# Slaves-Power-board.net
KiCad netlist of a schematic drawn in EAGLE
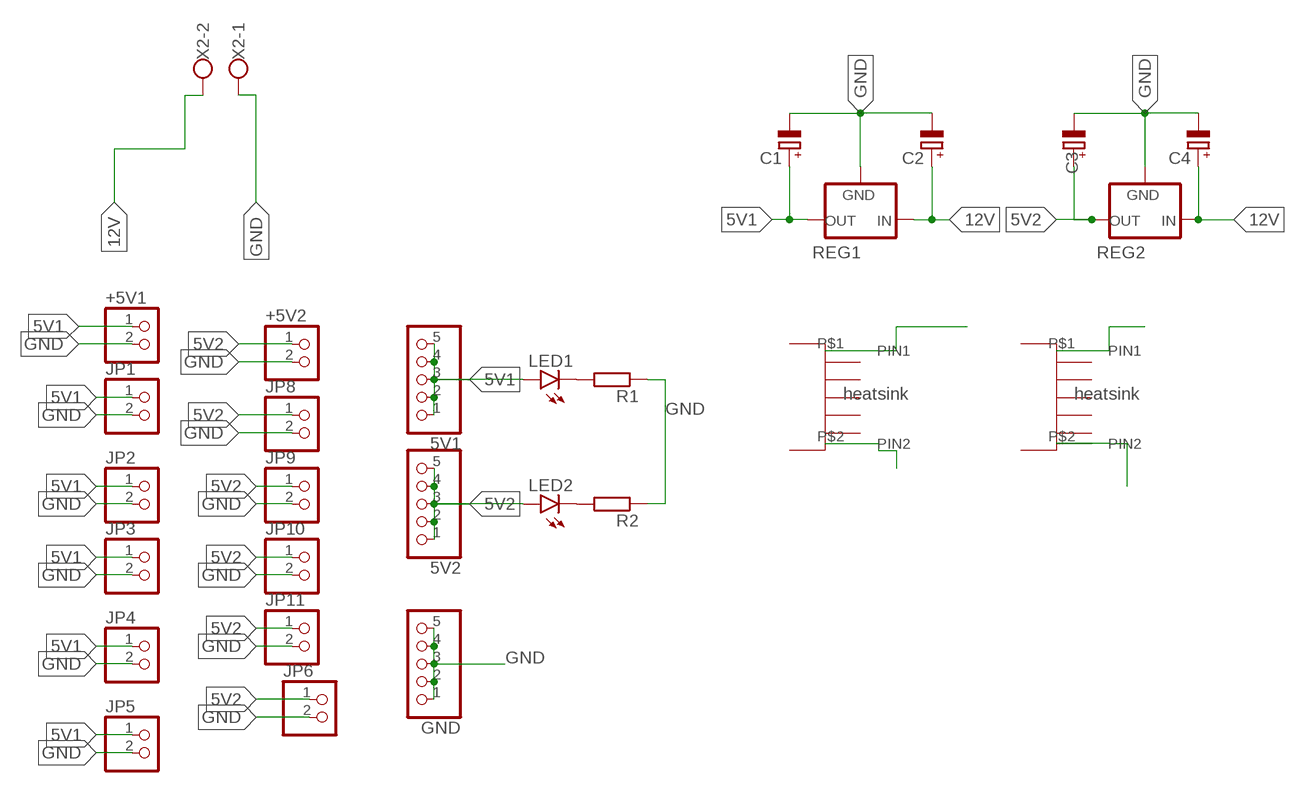
[diagram p0: schematic, sheet 1]

(export (version "E")
  (design (tool "Eeschema 10.0.6"))
  (components
    (comp (ref "+5V1")
      (value "PINHD-2_DATA")
      (footprint "eagle-import:1X02_DATA")
      (libsource (lib "eagle-import") (part "PINHD-2_DATA"))
    )
    (comp (ref "+5V2")
      (value "PINHD-2_DATA")
      (footprint "eagle-import:1X02_DATA")
      (libsource (lib "eagle-import") (part "PINHD-2_DATA"))
    )
    (comp (ref "5V1")
      (value "PINHD-1X5")
      (footprint "eagle-import:1X05")
      (libsource (lib "eagle-import") (part "PINHD-1X5"))
    )
    (comp (ref "5V2")
      (value "PINHD-1X5")
      (footprint "eagle-import:1X05")
      (libsource (lib "eagle-import") (part "PINHD-1X5"))
    )
    (comp (ref "C1")
      (value "CAP_POL")
      (footprint "eagle-import:E3,5-8")
      (libsource (lib "eagle-import") (part "CAP_POL"))
    )
    (comp (ref "C2")
      (value "CAP_POL")
      (footprint "eagle-import:E3,5-8")
      (libsource (lib "eagle-import") (part "CAP_POL"))
    )
    (comp (ref "C3")
      (value "CAP_POL")
      (footprint "eagle-import:E3,5-8")
      (libsource (lib "eagle-import") (part "CAP_POL"))
    )
    (comp (ref "C4")
      (value "CAP_POL")
      (footprint "eagle-import:E3,5-8")
      (libsource (lib "eagle-import") (part "CAP_POL"))
    )
    (comp (ref "GND")
      (value "PINHD-1X5")
      (footprint "eagle-import:1X05")
      (libsource (lib "eagle-import") (part "PINHD-1X5"))
    )
    (comp (ref "JP1")
      (value "PINHD-2_DATA")
      (footprint "eagle-import:1X02_DATA")
      (libsource (lib "eagle-import") (part "PINHD-2_DATA"))
    )
    (comp (ref "JP2")
      (value "PINHD-2_DATA")
      (footprint "eagle-import:1X02_DATA")
      (libsource (lib "eagle-import") (part "PINHD-2_DATA"))
    )
    (comp (ref "JP3")
      (value "PINHD-2_DATA")
      (footprint "eagle-import:1X02_DATA")
      (libsource (lib "eagle-import") (part "PINHD-2_DATA"))
    )
    (comp (ref "JP4")
      (value "PINHD-2_DATA")
      (footprint "eagle-import:1X02_DATA")
      (libsource (lib "eagle-import") (part "PINHD-2_DATA"))
    )
    (comp (ref "JP5")
      (value "PINHD-2_DATA")
      (footprint "eagle-import:1X02_DATA")
      (libsource (lib "eagle-import") (part "PINHD-2_DATA"))
    )
    (comp (ref "JP6")
      (value "PINHD-2_DATA")
      (footprint "eagle-import:1X02_DATA")
      (libsource (lib "eagle-import") (part "PINHD-2_DATA"))
    )
    (comp (ref "JP8")
      (value "PINHD-2_DATA")
      (footprint "eagle-import:1X02_DATA")
      (libsource (lib "eagle-import") (part "PINHD-2_DATA"))
    )
    (comp (ref "JP9")
      (value "PINHD-2_DATA")
      (footprint "eagle-import:1X02_DATA")
      (libsource (lib "eagle-import") (part "PINHD-2_DATA"))
    )
    (comp (ref "JP10")
      (value "PINHD-2_DATA")
      (footprint "eagle-import:1X02_DATA")
      (libsource (lib "eagle-import") (part "PINHD-2_DATA"))
    )
    (comp (ref "JP11")
      (value "PINHD-2_DATA")
      (footprint "eagle-import:1X02_DATA")
      (libsource (lib "eagle-import") (part "PINHD-2_DATA"))
    )
    (comp (ref "LED1")
      (value "LED5MM")
      (footprint "eagle-import:LED5MM")
      (libsource (lib "eagle-import") (part "LED5MM"))
    )
    (comp (ref "LED2")
      (value "LED5MM")
      (footprint "eagle-import:LED5MM")
      (libsource (lib "eagle-import") (part "LED5MM"))
    )
    (comp (ref "R1")
      (value "R-EU_0204/7")
      (footprint "eagle-import:0204_7")
      (libsource (lib "eagle-import") (part "R-EU_0204/7"))
    )
    (comp (ref "R2")
      (value "R-EU_0204/7")
      (footprint "eagle-import:0204_7")
      (libsource (lib "eagle-import") (part "R-EU_0204/7"))
    )
    (comp (ref "REG1")
      (value "78XXS")
      (footprint "eagle-import:78XXS")
      (libsource (lib "eagle-import") (part "78XXS"))
    )
    (comp (ref "REG2")
      (value "78XXS")
      (footprint "eagle-import:78XXS")
      (libsource (lib "eagle-import") (part "78XXS"))
    )
    (comp (ref "U$1")
      (value "HEAT-SINK")
      (footprint "eagle-import:HEAT_SINK")
      (libsource (lib "eagle-import") (part "HEAT-SINK"))
    )
    (comp (ref "U$2")
      (value "HEAT-SINK")
      (footprint "eagle-import:HEAT_SINK")
      (libsource (lib "eagle-import") (part "HEAT-SINK"))
    )
    (comp (ref "X2")
      (value "ROSTA.POWER")
      (footprint "eagle-import:W239-302")
      (libsource (lib "eagle-import") (part "ROSTA.POWER"))
    )
  )
  (nets
    (net (code "1") (name "5V1") (class "Default")
      (node (ref "+5V1") (pin "1") (pinfunction "1_1") (pintype "passive"))
      (node (ref "5V1") (pin "1") (pinfunction "1_1") (pintype "passive"))
      (node (ref "5V1") (pin "2") (pinfunction "2_2") (pintype "passive"))
      (node (ref "5V1") (pin "3") (pinfunction "3_3") (pintype "passive"))
      (node (ref "5V1") (pin "4") (pinfunction "4_4") (pintype "passive"))
      (node (ref "5V1") (pin "5") (pinfunction "5_5") (pintype "passive"))
      (node (ref "C1") (pin "+") (pinfunction "+_+") (pintype "passive"))
      (node (ref "JP1") (pin "1") (pinfunction "1_1") (pintype "passive"))
      (node (ref "JP2") (pin "1") (pinfunction "1_1") (pintype "passive"))
      (node (ref "JP3") (pin "1") (pinfunction "1_1") (pintype "passive"))
      (node (ref "JP4") (pin "1") (pinfunction "1_1") (pintype "passive"))
      (node (ref "JP5") (pin "1") (pinfunction "1_1") (pintype "passive"))
      (node (ref "LED1") (pin "A") (pinfunction "A_A") (pintype "passive"))
      (node (ref "REG1") (pin "OUT") (pinfunction "OUT_OUT") (pintype "passive"))
    )
    (net (code "2") (name "5V2") (class "Default")
      (node (ref "+5V2") (pin "1") (pinfunction "1_1") (pintype "passive"))
      (node (ref "5V2") (pin "1") (pinfunction "1_1") (pintype "passive"))
      (node (ref "5V2") (pin "2") (pinfunction "2_2") (pintype "passive"))
      (node (ref "5V2") (pin "3") (pinfunction "3_3") (pintype "passive"))
      (node (ref "5V2") (pin "4") (pinfunction "4_4") (pintype "passive"))
      (node (ref "5V2") (pin "5") (pinfunction "5_5") (pintype "passive"))
      (node (ref "C3") (pin "+") (pinfunction "+_+") (pintype "passive"))
      (node (ref "JP10") (pin "1") (pinfunction "1_1") (pintype "passive"))
      (node (ref "JP11") (pin "1") (pinfunction "1_1") (pintype "passive"))
      (node (ref "JP6") (pin "1") (pinfunction "1_1") (pintype "passive"))
      (node (ref "JP8") (pin "1") (pinfunction "1_1") (pintype "passive"))
      (node (ref "JP9") (pin "1") (pinfunction "1_1") (pintype "passive"))
      (node (ref "LED2") (pin "A") (pinfunction "A_A") (pintype "passive"))
      (node (ref "REG2") (pin "OUT") (pinfunction "OUT_OUT") (pintype "passive"))
    )
    (net (code "3") (name "12V") (class "Default")
      (node (ref "C2") (pin "+") (pinfunction "+_+") (pintype "passive"))
      (node (ref "C4") (pin "+") (pinfunction "+_+") (pintype "passive"))
      (node (ref "REG1") (pin "IN") (pinfunction "IN_IN") (pintype "input"))
      (node (ref "REG2") (pin "IN") (pinfunction "IN_IN") (pintype "input"))
      (node (ref "X2") (pin "2") (pinfunction "KL_2") (pintype "passive"))
    )
    (net (code "4") (name "GND") (class "Default")
      (node (ref "+5V1") (pin "2") (pinfunction "2_2") (pintype "passive"))
      (node (ref "+5V2") (pin "2") (pinfunction "2_2") (pintype "passive"))
      (node (ref "C1") (pin "-") (pinfunction "-_-") (pintype "passive"))
      (node (ref "C2") (pin "-") (pinfunction "-_-") (pintype "passive"))
      (node (ref "C3") (pin "-") (pinfunction "-_-") (pintype "passive"))
      (node (ref "C4") (pin "-") (pinfunction "-_-") (pintype "passive"))
      (node (ref "GND") (pin "1") (pinfunction "1_1") (pintype "passive"))
      (node (ref "GND") (pin "2") (pinfunction "2_2") (pintype "passive"))
      (node (ref "GND") (pin "3") (pinfunction "3_3") (pintype "passive"))
      (node (ref "GND") (pin "4") (pinfunction "4_4") (pintype "passive"))
      (node (ref "GND") (pin "5") (pinfunction "5_5") (pintype "passive"))
      (node (ref "JP1") (pin "2") (pinfunction "2_2") (pintype "passive"))
      (node (ref "JP10") (pin "2") (pinfunction "2_2") (pintype "passive"))
      (node (ref "JP11") (pin "2") (pinfunction "2_2") (pintype "passive"))
      (node (ref "JP2") (pin "2") (pinfunction "2_2") (pintype "passive"))
      (node (ref "JP3") (pin "2") (pinfunction "2_2") (pintype "passive"))
      (node (ref "JP4") (pin "2") (pinfunction "2_2") (pintype "passive"))
      (node (ref "JP5") (pin "2") (pinfunction "2_2") (pintype "passive"))
      (node (ref "JP6") (pin "2") (pinfunction "2_2") (pintype "passive"))
      (node (ref "JP8") (pin "2") (pinfunction "2_2") (pintype "passive"))
      (node (ref "JP9") (pin "2") (pinfunction "2_2") (pintype "passive"))
      (node (ref "R1") (pin "1") (pinfunction "1_1") (pintype "passive"))
      (node (ref "R2") (pin "1") (pinfunction "1_1") (pintype "passive"))
      (node (ref "REG1") (pin "GND") (pinfunction "GND_GND") (pintype "input"))
      (node (ref "REG2") (pin "GND") (pinfunction "GND_GND") (pintype "input"))
      (node (ref "X2") (pin "1") (pinfunction "KL_1") (pintype "passive"))
    )
    (net (code "5") (name "Net-(LED1-C)") (class "Default")
      (node (ref "LED1") (pin "K") (pinfunction "C_K") (pintype "passive"))
      (node (ref "R1") (pin "2") (pinfunction "2_2") (pintype "passive"))
    )
    (net (code "6") (name "Net-(LED2-C)") (class "Default")
      (node (ref "LED2") (pin "K") (pinfunction "C_K") (pintype "passive"))
      (node (ref "R2") (pin "2") (pinfunction "2_2") (pintype "passive"))
    )
    (net (code "7") (name "unconnected-(U$1-PIN1-PadP$1)") (class "Default")
      (node (ref "U$1") (pin "P$1") (pinfunction "PIN1_P$1") (pintype "bidirectional"))
    )
    (net (code "8") (name "unconnected-(U$1-PIN2-PadP$2)") (class "Default")
      (node (ref "U$1") (pin "P$2") (pinfunction "PIN2_P$2") (pintype "bidirectional"))
    )
    (net (code "9") (name "unconnected-(U$2-PIN1-PadP$1)") (class "Default")
      (node (ref "U$2") (pin "P$1") (pinfunction "PIN1_P$1") (pintype "bidirectional"))
    )
    (net (code "10") (name "unconnected-(U$2-PIN2-PadP$2)") (class "Default")
      (node (ref "U$2") (pin "P$2") (pinfunction "PIN2_P$2") (pintype "bidirectional"))
    )
  )
)
